# MCB-MTS-Dragonfly-v2_0_0.net
KiCad netlist of a schematic drawn in EAGLE
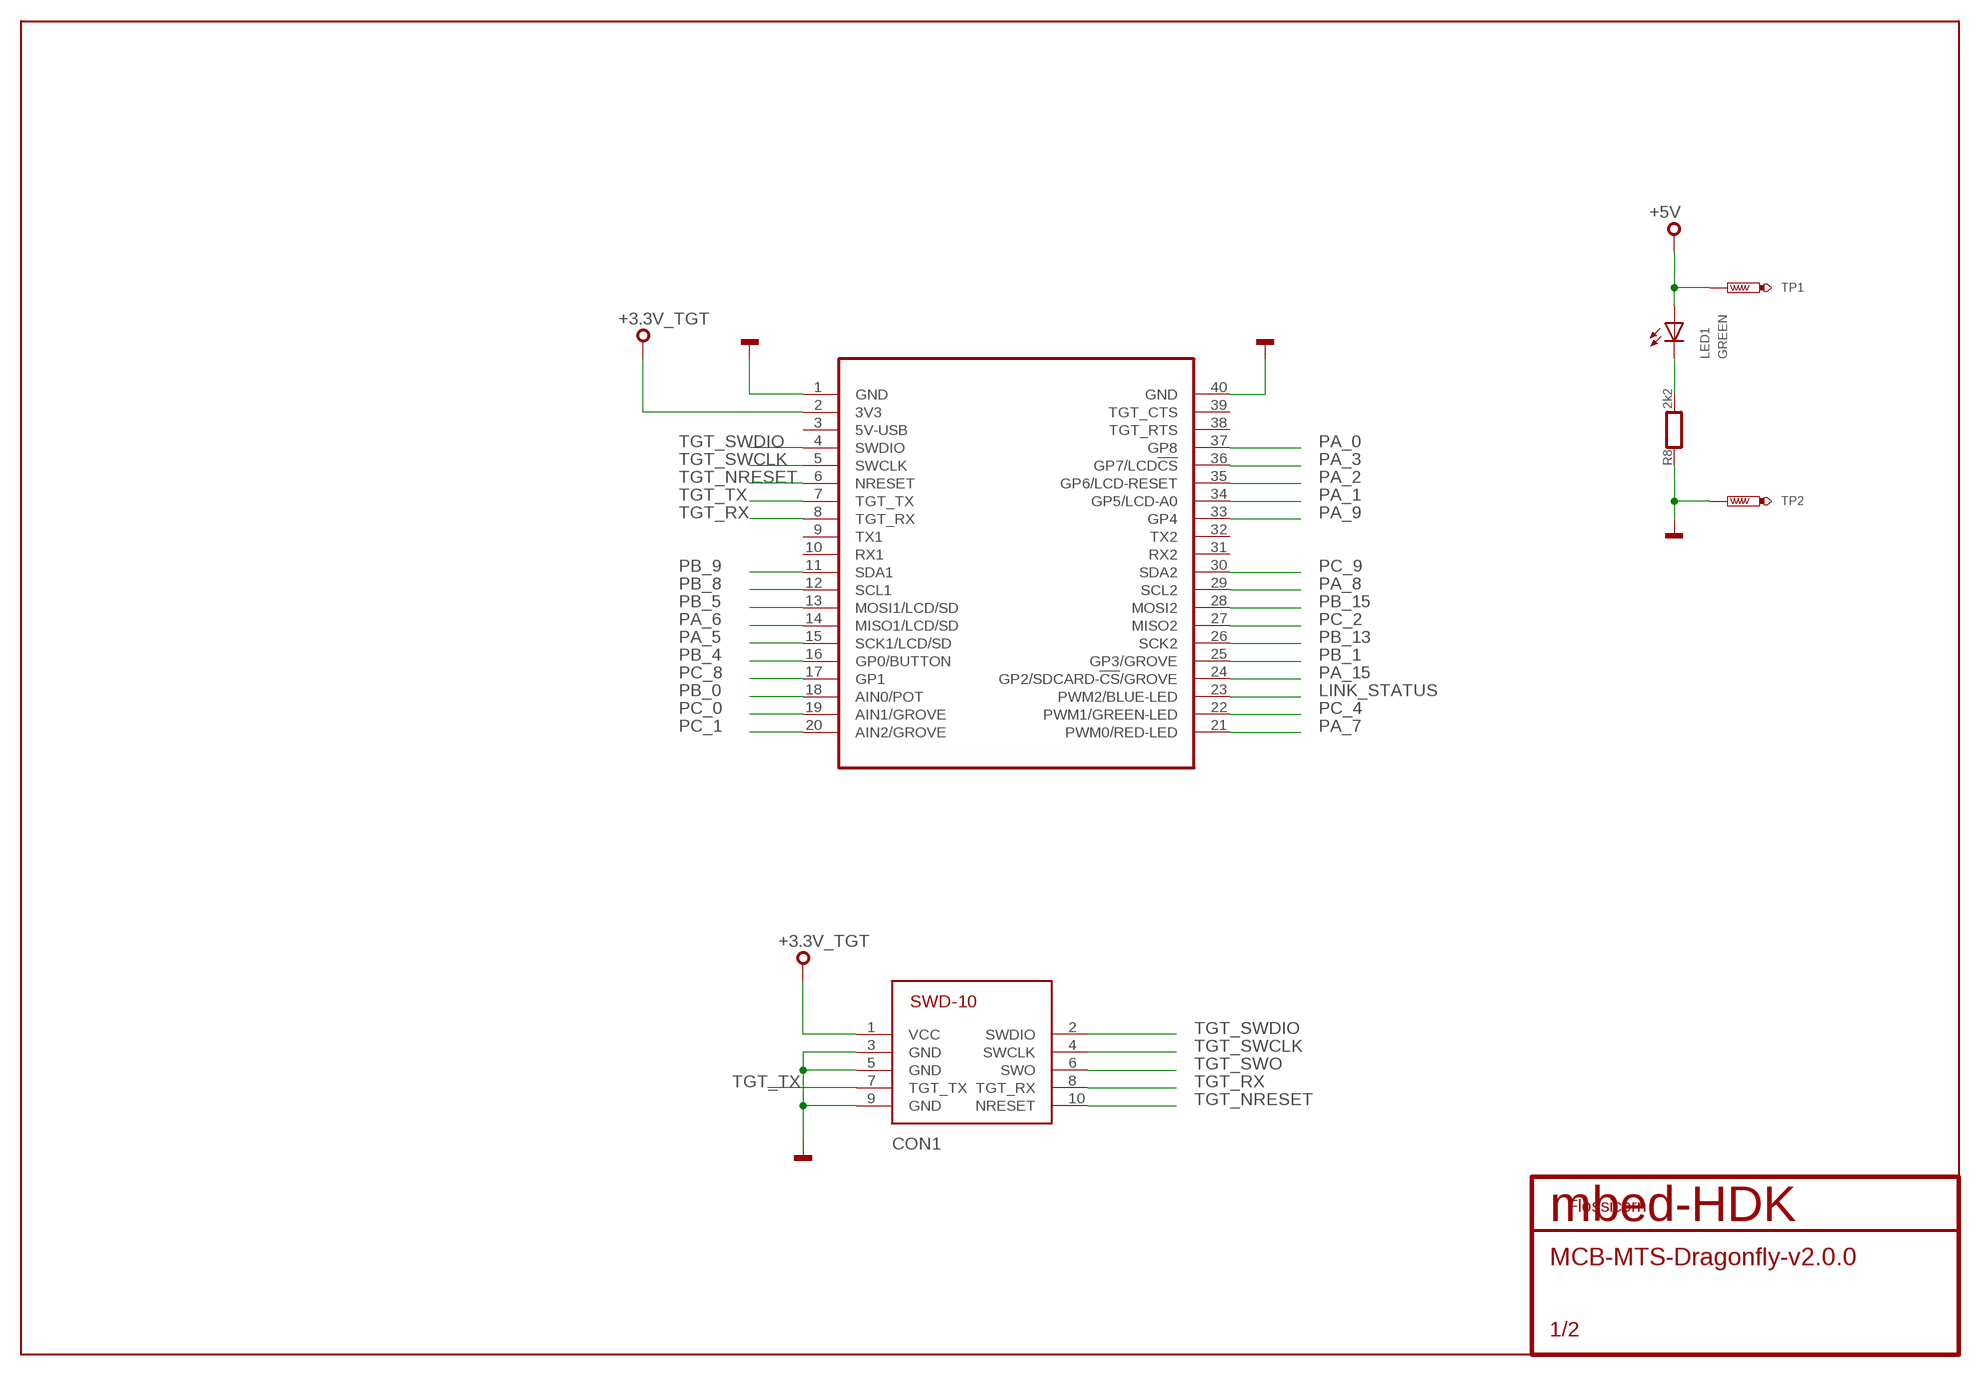
[diagram p0: schematic, sheet 1]
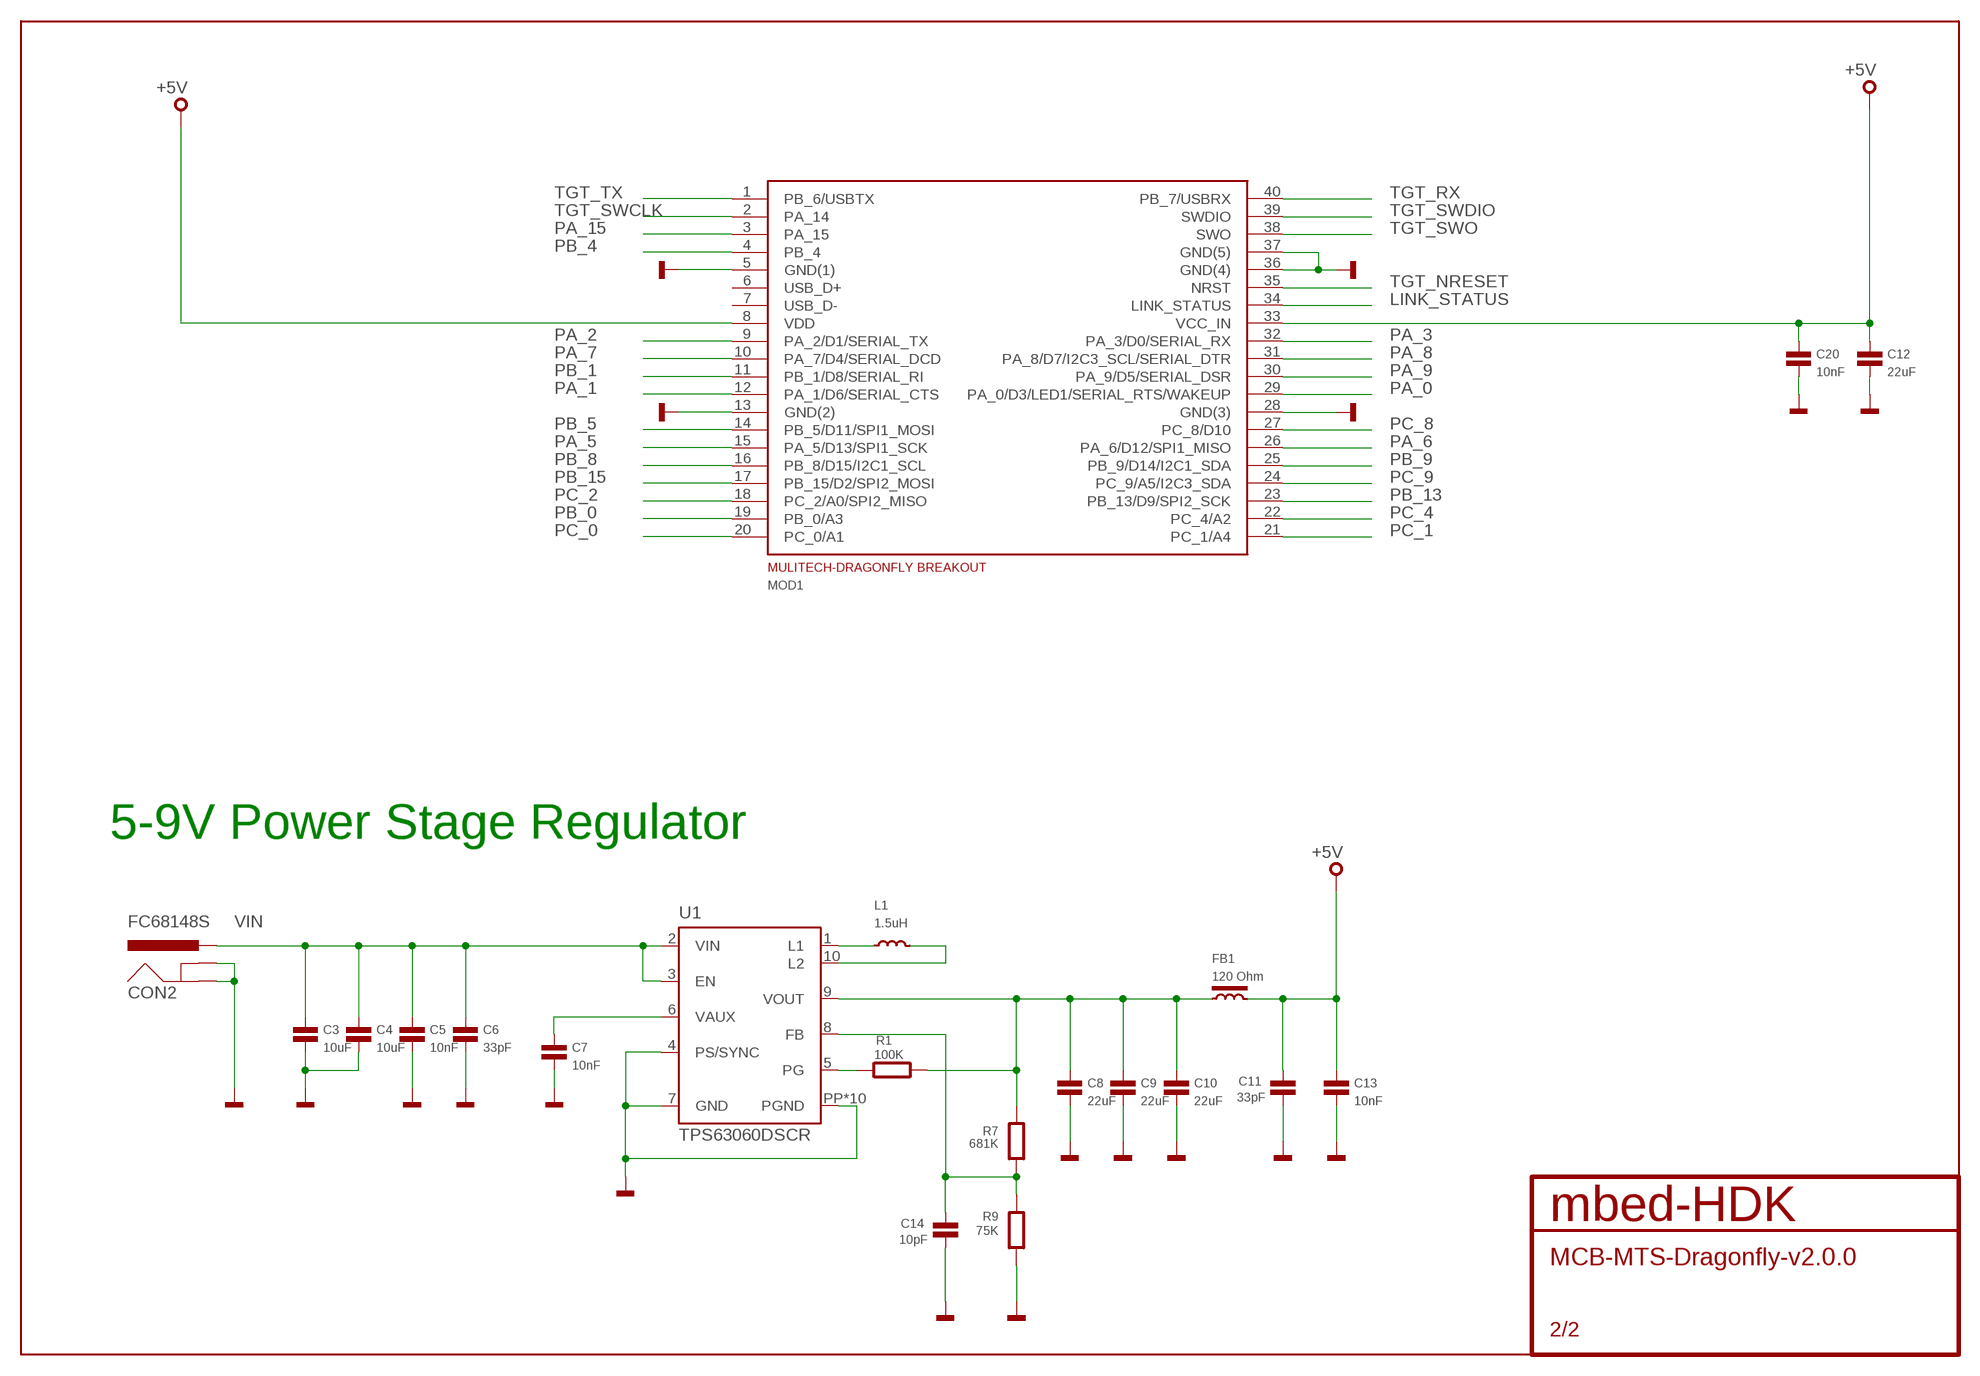
[diagram p1: schematic, sheet 2]

(export (version "E")
  (design (tool "Eeschema 10.0.6"))
  (components
    (comp (ref "CON1")
      (value "SWD-10/TC2050_SMD")
      (footprint "eagle-import:FTSH-105-02")
      (libsource (lib "eagle-import") (part "SWD-10/TC2050_SMD"))
    )
    (comp (ref "LED1")
      (value "GREEN")
      (footprint "eagle-import:CHIPLED_0603")
      (fields (field (name "MF") "Wurth Electronics Inc"))
      (libsource (lib "eagle-import") (part "SMD_LED0603"))
    )
    (comp (ref "MOD2")
      (value "MODULE_DAUGHTER")
      (footprint "eagle-import:MODULE_DAUGHTER")
      (libsource (lib "eagle-import") (part "MODULE_DAUGHTER"))
    )
    (comp (ref "R8")
      (value "2k2")
      (footprint "eagle-import:0603")
      (libsource (lib "eagle-import") (part "RESISTOR0603"))
    )
    (comp (ref "SS1")
      (value "FLOSSICORN0.5")
      (footprint "eagle-import:FLOSSICORN-0.5")
      (libsource (lib "eagle-import") (part "FLOSSICORN0.5"))
    )
    (comp (ref "TP1")
      (value "TEST-POINT-50R-PTH")
      (footprint "eagle-import:TP50-PTH")
      (libsource (lib "eagle-import") (part "TEST-POINT-50R-PTH"))
    )
    (comp (ref "TP2")
      (value "TEST-POINT-50R-PTH")
      (footprint "eagle-import:TP50-PTH")
      (libsource (lib "eagle-import") (part "TEST-POINT-50R-PTH"))
    )
    (comp (ref "C3")
      (value "10uF")
      (footprint "eagle-import:0603")
      (libsource (lib "eagle-import") (part "CAPACITOR0603"))
    )
    (comp (ref "C4")
      (value "10uF")
      (footprint "eagle-import:0603")
      (libsource (lib "eagle-import") (part "CAPACITOR0603"))
    )
    (comp (ref "C5")
      (value "10nF")
      (footprint "eagle-import:0603")
      (libsource (lib "eagle-import") (part "CAPACITOR0603"))
    )
    (comp (ref "C6")
      (value "33pF")
      (footprint "eagle-import:0603")
      (libsource (lib "eagle-import") (part "CAPACITOR0603"))
    )
    (comp (ref "C7")
      (value "10nF")
      (footprint "eagle-import:0603")
      (libsource (lib "eagle-import") (part "CAPACITOR0603"))
    )
    (comp (ref "C8")
      (value "22uF")
      (footprint "eagle-import:0603")
      (libsource (lib "eagle-import") (part "CAPACITOR0603"))
    )
    (comp (ref "C9")
      (value "22uF")
      (footprint "eagle-import:0603")
      (libsource (lib "eagle-import") (part "CAPACITOR0603"))
    )
    (comp (ref "C10")
      (value "22uF")
      (footprint "eagle-import:0603")
      (libsource (lib "eagle-import") (part "CAPACITOR0603"))
    )
    (comp (ref "C11")
      (value "33pF")
      (footprint "eagle-import:0603")
      (libsource (lib "eagle-import") (part "CAPACITOR0603"))
    )
    (comp (ref "C12")
      (value "22uF")
      (footprint "eagle-import:0603")
      (libsource (lib "eagle-import") (part "CAPACITOR0603"))
    )
    (comp (ref "C13")
      (value "10nF")
      (footprint "eagle-import:0603")
      (libsource (lib "eagle-import") (part "CAPACITOR0603"))
    )
    (comp (ref "C14")
      (value "10pF")
      (footprint "eagle-import:0603")
      (libsource (lib "eagle-import") (part "CAPACITOR0603"))
    )
    (comp (ref "C20")
      (value "10nF")
      (footprint "eagle-import:0603")
      (libsource (lib "eagle-import") (part "CAPACITOR0603"))
    )
    (comp (ref "CON2")
      (value "FC68148S")
      (footprint "eagle-import:FC68148S")
      (libsource (lib "eagle-import") (part "FC68148S"))
    )
    (comp (ref "FB1")
      (value "120 Ohm")
      (footprint "eagle-import:0603")
      (libsource (lib "eagle-import") (part "FERRITE0603"))
    )
    (comp (ref "L1")
      (value "1.5uH")
      (footprint "eagle-import:XFL4020-472MEC")
      (fields (field (name "MF") "CoilCraft"))
      (libsource (lib "eagle-import") (part "INDUCTORXFL4020"))
    )
    (comp (ref "MOD1")
      (value "MULITECH-DRAGONFLY-BREAKOUT")
      (footprint "eagle-import:MULITECH-DRAGONFLY-BREAKOUT")
      (fields (field (name "MF") "Hirose"))
      (libsource (lib "eagle-import") (part "MULITECH-DRAGONFLY-BREAKOUT"))
    )
    (comp (ref "R1")
      (value "100K")
      (footprint "eagle-import:0402")
      (libsource (lib "eagle-import") (part "mbed-HDK-RLCQ_RESISTOR0402"))
    )
    (comp (ref "R7")
      (value "681K")
      (footprint "eagle-import:0402")
      (libsource (lib "eagle-import") (part "mbed-HDK-RLCQ_RESISTOR0402"))
    )
    (comp (ref "R9")
      (value "75K")
      (footprint "eagle-import:0402")
      (libsource (lib "eagle-import") (part "mbed-HDK-RLCQ_RESISTOR0402"))
    )
    (comp (ref "U1")
      (value "TPS63060DSCR")
      (footprint "eagle-import:DSC-S-PWSON-N10")
      (fields (field (name "MF") "TEXAS INSTRUMENTS"))
      (libsource (lib "eagle-import") (part "TPS63060DSCR"))
    )
  )
  (nets
    (net (code "1") (name "+3.3V_TGT") (class "Default")
      (node (ref "CON1") (pin "1") (pinfunction "VCC_1") (pintype "bidirectional"))
      (node (ref "MOD2") (pin "2") (pinfunction "3V3_2") (pintype "bidirectional"))
    )
    (net (code "2") (name "+5V") (class "Default")
      (node (ref "C11") (pin "1") (pinfunction "P$1_1") (pintype "passive"))
      (node (ref "C12") (pin "1") (pinfunction "P$1_1") (pintype "passive"))
      (node (ref "C13") (pin "1") (pinfunction "P$1_1") (pintype "passive"))
      (node (ref "C20") (pin "1") (pinfunction "P$1_1") (pintype "passive"))
      (node (ref "FB1") (pin "2") (pinfunction "P$2_2") (pintype "bidirectional"))
      (node (ref "LED1") (pin "A") (pinfunction "A_A") (pintype "passive"))
      (node (ref "MOD1") (pin "33") (pinfunction "VCC_IN_33") (pintype "bidirectional"))
      (node (ref "MOD1") (pin "8") (pinfunction "VDD_8") (pintype "bidirectional"))
      (node (ref "TP1") (pin "TP") (pinfunction "TP_TP") (pintype "input"))
    )
    (net (code "3") (name "GND") (class "Default")
      (node (ref "C10") (pin "2") (pinfunction "P$2_2") (pintype "passive"))
      (node (ref "C11") (pin "2") (pinfunction "P$2_2") (pintype "passive"))
      (node (ref "C12") (pin "2") (pinfunction "P$2_2") (pintype "passive"))
      (node (ref "C13") (pin "2") (pinfunction "P$2_2") (pintype "passive"))
      (node (ref "C14") (pin "2") (pinfunction "P$2_2") (pintype "passive"))
      (node (ref "C20") (pin "2") (pinfunction "P$2_2") (pintype "passive"))
      (node (ref "C3") (pin "2") (pinfunction "P$2_2") (pintype "passive"))
      (node (ref "C4") (pin "2") (pinfunction "P$2_2") (pintype "passive"))
      (node (ref "C5") (pin "2") (pinfunction "P$2_2") (pintype "passive"))
      (node (ref "C6") (pin "2") (pinfunction "P$2_2") (pintype "passive"))
      (node (ref "C7") (pin "2") (pinfunction "P$2_2") (pintype "passive"))
      (node (ref "C8") (pin "2") (pinfunction "P$2_2") (pintype "passive"))
      (node (ref "C9") (pin "2") (pinfunction "P$2_2") (pintype "passive"))
      (node (ref "CON1") (pin "3") (pinfunction "GND_3") (pintype "bidirectional"))
      (node (ref "CON1") (pin "5") (pinfunction "GND_5") (pintype "bidirectional"))
      (node (ref "CON1") (pin "9") (pinfunction "GND_9") (pintype "bidirectional"))
      (node (ref "CON2") (pin "2") (pinfunction "GNDBREAK_2") (pintype "bidirectional"))
      (node (ref "CON2") (pin "3") (pinfunction "GND_3") (pintype "bidirectional"))
      (node (ref "MOD1") (pin "13") (pinfunction "GND(2)_13") (pintype "bidirectional"))
      (node (ref "MOD1") (pin "28") (pinfunction "GND(3)_28") (pintype "bidirectional"))
      (node (ref "MOD1") (pin "36") (pinfunction "GND(4)_36") (pintype "bidirectional"))
      (node (ref "MOD1") (pin "37") (pinfunction "GND(5)_37") (pintype "bidirectional"))
      (node (ref "MOD1") (pin "5") (pinfunction "GND(1)_5") (pintype "bidirectional"))
      (node (ref "MOD2") (pin "1") (pinfunction "GND_1") (pintype "bidirectional"))
      (node (ref "MOD2") (pin "40") (pinfunction "GND_40") (pintype "bidirectional"))
      (node (ref "R8") (pin "1") (pinfunction "P$1_1") (pintype "passive"))
      (node (ref "R9") (pin "1") (pinfunction "P$1_1") (pintype "passive"))
      (node (ref "TP2") (pin "TP") (pinfunction "TP_TP") (pintype "input"))
      (node (ref "U1") (pin "4") (pinfunction "PS/SYNC_4") (pintype "input"))
      (node (ref "U1") (pin "7") (pinfunction "GND_7") (pintype "input"))
      (node (ref "U1") (pin "PP") (pinfunction "PGND_PP") (pintype "power_in"))
      (node (ref "U1") (pin "PP@1") (pinfunction "PGND_PP@1") (pintype "power_in"))
      (node (ref "U1") (pin "PP@10") (pinfunction "PGND_PP@10") (pintype "power_in"))
      (node (ref "U1") (pin "PP@2") (pinfunction "PGND_PP@2") (pintype "power_in"))
      (node (ref "U1") (pin "PP@3") (pinfunction "PGND_PP@3") (pintype "power_in"))
      (node (ref "U1") (pin "PP@4") (pinfunction "PGND_PP@4") (pintype "power_in"))
      (node (ref "U1") (pin "PP@5") (pinfunction "PGND_PP@5") (pintype "power_in"))
      (node (ref "U1") (pin "PP@7") (pinfunction "PGND_PP@7") (pintype "power_in"))
      (node (ref "U1") (pin "PP@8") (pinfunction "PGND_PP@8") (pintype "power_in"))
      (node (ref "U1") (pin "PP@9") (pinfunction "PGND_PP@9") (pintype "power_in"))
    )
    (net (code "4") (name "LINK_STATUS") (class "Default")
      (node (ref "MOD1") (pin "34") (pinfunction "LINK_STATUS_34") (pintype "bidirectional"))
      (node (ref "MOD2") (pin "23") (pinfunction "PWM2/BLUE-LED_23") (pintype "bidirectional"))
    )
    (net (code "5") (name "Net-(C7-P$1)") (class "Default")
      (node (ref "C7") (pin "1") (pinfunction "P$1_1") (pintype "passive"))
      (node (ref "U1") (pin "6") (pinfunction "VAUX_6") (pintype "power_in"))
    )
    (net (code "6") (name "Net-(C10-P$1)") (class "Default")
      (node (ref "C10") (pin "1") (pinfunction "P$1_1") (pintype "passive"))
      (node (ref "C8") (pin "1") (pinfunction "P$1_1") (pintype "passive"))
      (node (ref "C9") (pin "1") (pinfunction "P$1_1") (pintype "passive"))
      (node (ref "FB1") (pin "1") (pinfunction "P$1_1") (pintype "bidirectional"))
      (node (ref "R1") (pin "2") (pinfunction "P$2_2") (pintype "passive"))
      (node (ref "R7") (pin "2") (pinfunction "P$2_2") (pintype "passive"))
      (node (ref "U1") (pin "9") (pinfunction "VOUT_9") (pintype "output"))
    )
    (net (code "7") (name "Net-(C14-P$1)") (class "Default")
      (node (ref "C14") (pin "1") (pinfunction "P$1_1") (pintype "passive"))
      (node (ref "R7") (pin "1") (pinfunction "P$1_1") (pintype "passive"))
      (node (ref "R9") (pin "2") (pinfunction "P$2_2") (pintype "passive"))
      (node (ref "U1") (pin "8") (pinfunction "FB_8") (pintype "input"))
    )
    (net (code "8") (name "Net-(R1-P$1)") (class "Default")
      (node (ref "R1") (pin "1") (pinfunction "P$1_1") (pintype "passive"))
      (node (ref "U1") (pin "5") (pinfunction "PG_5") (pintype "output"))
    )
    (net (code "9") (name "Net-(R8-P$2)") (class "Default")
      (node (ref "LED1") (pin "C") (pinfunction "C_C") (pintype "passive"))
      (node (ref "R8") (pin "2") (pinfunction "P$2_2") (pintype "passive"))
    )
    (net (code "10") (name "Net-(U1-L1)") (class "Default")
      (node (ref "L1") (pin "P$1") (pinfunction "P$1_P$1") (pintype "bidirectional"))
      (node (ref "U1") (pin "1") (pinfunction "L1_1") (pintype "input"))
    )
    (net (code "11") (name "Net-(U1-L2)") (class "Default")
      (node (ref "L1") (pin "P$2") (pinfunction "P$2_P$2") (pintype "bidirectional"))
      (node (ref "U1") (pin "10") (pinfunction "L2_10") (pintype "input"))
    )
    (net (code "12") (name "PA_0") (class "Default")
      (node (ref "MOD1") (pin "29") (pinfunction "PA_0/D3/LED1/SERIAL_RTS/WAKEUP_29") (pintype "bidirectional"))
      (node (ref "MOD2") (pin "37") (pinfunction "GP8_37") (pintype "bidirectional"))
    )
    (net (code "13") (name "PA_1") (class "Default")
      (node (ref "MOD1") (pin "12") (pinfunction "PA_1/D6/SERIAL_CTS_12") (pintype "bidirectional"))
      (node (ref "MOD2") (pin "34") (pinfunction "GP5/LCD-A0_34") (pintype "bidirectional"))
    )
    (net (code "14") (name "PA_2") (class "Default")
      (node (ref "MOD1") (pin "9") (pinfunction "PA_2/D1/SERIAL_TX_9") (pintype "bidirectional"))
      (node (ref "MOD2") (pin "35") (pinfunction "GP6/LCD-RESET_35") (pintype "bidirectional"))
    )
    (net (code "15") (name "PA_3") (class "Default")
      (node (ref "MOD1") (pin "32") (pinfunction "PA_3/D0/SERIAL_RX_32") (pintype "bidirectional"))
      (node (ref "MOD2") (pin "36") (pinfunction "GP7/LCD~{CS}_36") (pintype "bidirectional"))
    )
    (net (code "16") (name "PA_5") (class "Default")
      (node (ref "MOD1") (pin "15") (pinfunction "PA_5/D13/SPI1_SCK_15") (pintype "bidirectional"))
      (node (ref "MOD2") (pin "15") (pinfunction "SCK1/LCD/SD_15") (pintype "bidirectional"))
    )
    (net (code "17") (name "PA_6") (class "Default")
      (node (ref "MOD1") (pin "26") (pinfunction "PA_6/D12/SPI1_MISO_26") (pintype "bidirectional"))
      (node (ref "MOD2") (pin "14") (pinfunction "MISO1/LCD/SD_14") (pintype "bidirectional"))
    )
    (net (code "18") (name "PA_7") (class "Default")
      (node (ref "MOD1") (pin "10") (pinfunction "PA_7/D4/SERIAL_DCD_10") (pintype "bidirectional"))
      (node (ref "MOD2") (pin "21") (pinfunction "PWM0/RED-LED_21") (pintype "bidirectional"))
    )
    (net (code "19") (name "PA_8") (class "Default")
      (node (ref "MOD1") (pin "31") (pinfunction "PA_8/D7/I2C3_SCL/SERIAL_DTR_31") (pintype "bidirectional"))
      (node (ref "MOD2") (pin "29") (pinfunction "SCL2_29") (pintype "bidirectional"))
    )
    (net (code "20") (name "PA_9") (class "Default")
      (node (ref "MOD1") (pin "30") (pinfunction "PA_9/D5/SERIAL_DSR_30") (pintype "bidirectional"))
      (node (ref "MOD2") (pin "33") (pinfunction "GP4_33") (pintype "bidirectional"))
    )
    (net (code "21") (name "PA_15") (class "Default")
      (node (ref "MOD1") (pin "3") (pinfunction "PA_15_3") (pintype "bidirectional"))
      (node (ref "MOD2") (pin "24") (pinfunction "GP2/SDCARD-~{CS}/GROVE_24") (pintype "bidirectional"))
    )
    (net (code "22") (name "PB_0") (class "Default")
      (node (ref "MOD1") (pin "19") (pinfunction "PB_0/A3_19") (pintype "bidirectional"))
      (node (ref "MOD2") (pin "18") (pinfunction "AIN0/POT_18") (pintype "bidirectional"))
    )
    (net (code "23") (name "PB_1") (class "Default")
      (node (ref "MOD1") (pin "11") (pinfunction "PB_1/D8/SERIAL_RI_11") (pintype "bidirectional"))
      (node (ref "MOD2") (pin "25") (pinfunction "GP3/GROVE_25") (pintype "bidirectional"))
    )
    (net (code "24") (name "PB_4") (class "Default")
      (node (ref "MOD1") (pin "4") (pinfunction "PB_4_4") (pintype "bidirectional"))
      (node (ref "MOD2") (pin "16") (pinfunction "GP0/BUTTON_16") (pintype "bidirectional"))
    )
    (net (code "25") (name "PB_5") (class "Default")
      (node (ref "MOD1") (pin "14") (pinfunction "PB_5/D11/SPI1_MOSI_14") (pintype "bidirectional"))
      (node (ref "MOD2") (pin "13") (pinfunction "MOSI1/LCD/SD_13") (pintype "bidirectional"))
    )
    (net (code "26") (name "PB_8") (class "Default")
      (node (ref "MOD1") (pin "16") (pinfunction "PB_8/D15/I2C1_SCL_16") (pintype "bidirectional"))
      (node (ref "MOD2") (pin "12") (pinfunction "SCL1_12") (pintype "bidirectional"))
    )
    (net (code "27") (name "PB_9") (class "Default")
      (node (ref "MOD1") (pin "25") (pinfunction "PB_9/D14/I2C1_SDA_25") (pintype "bidirectional"))
      (node (ref "MOD2") (pin "11") (pinfunction "SDA1_11") (pintype "bidirectional"))
    )
    (net (code "28") (name "PB_13") (class "Default")
      (node (ref "MOD1") (pin "23") (pinfunction "PB_13/D9/SPI2_SCK_23") (pintype "bidirectional"))
      (node (ref "MOD2") (pin "26") (pinfunction "SCK2_26") (pintype "bidirectional"))
    )
    (net (code "29") (name "PB_15") (class "Default")
      (node (ref "MOD1") (pin "17") (pinfunction "PB_15/D2/SPI2_MOSI_17") (pintype "bidirectional"))
      (node (ref "MOD2") (pin "28") (pinfunction "MOSI2_28") (pintype "bidirectional"))
    )
    (net (code "30") (name "PC_0") (class "Default")
      (node (ref "MOD1") (pin "20") (pinfunction "PC_0/A1_20") (pintype "bidirectional"))
      (node (ref "MOD2") (pin "19") (pinfunction "AIN1/GROVE_19") (pintype "bidirectional"))
    )
    (net (code "31") (name "PC_1") (class "Default")
      (node (ref "MOD1") (pin "21") (pinfunction "PC_1/A4_21") (pintype "bidirectional"))
      (node (ref "MOD2") (pin "20") (pinfunction "AIN2/GROVE_20") (pintype "bidirectional"))
    )
    (net (code "32") (name "PC_2") (class "Default")
      (node (ref "MOD1") (pin "18") (pinfunction "PC_2/A0/SPI2_MISO_18") (pintype "bidirectional"))
      (node (ref "MOD2") (pin "27") (pinfunction "MISO2_27") (pintype "bidirectional"))
    )
    (net (code "33") (name "PC_4") (class "Default")
      (node (ref "MOD1") (pin "22") (pinfunction "PC_4/A2_22") (pintype "bidirectional"))
      (node (ref "MOD2") (pin "22") (pinfunction "PWM1/GREEN-LED_22") (pintype "bidirectional"))
    )
    (net (code "34") (name "PC_8") (class "Default")
      (node (ref "MOD1") (pin "27") (pinfunction "PC_8/D10_27") (pintype "bidirectional"))
      (node (ref "MOD2") (pin "17") (pinfunction "GP1_17") (pintype "bidirectional"))
    )
    (net (code "35") (name "PC_9") (class "Default")
      (node (ref "MOD1") (pin "24") (pinfunction "PC_9/A5/I2C3_SDA_24") (pintype "bidirectional"))
      (node (ref "MOD2") (pin "30") (pinfunction "SDA2_30") (pintype "bidirectional"))
    )
    (net (code "36") (name "TGT_NRESET") (class "Default")
      (node (ref "CON1") (pin "10") (pinfunction "NRESET_10") (pintype "bidirectional"))
      (node (ref "MOD1") (pin "35") (pinfunction "NRST_35") (pintype "bidirectional"))
      (node (ref "MOD2") (pin "6") (pinfunction "NRESET_6") (pintype "bidirectional"))
    )
    (net (code "37") (name "TGT_RX") (class "Default")
      (node (ref "CON1") (pin "8") (pinfunction "TGT_RX_8") (pintype "bidirectional"))
      (node (ref "MOD1") (pin "40") (pinfunction "PB_7/USBRX_40") (pintype "bidirectional"))
      (node (ref "MOD2") (pin "8") (pinfunction "TGT_RX_8") (pintype "bidirectional"))
    )
    (net (code "38") (name "TGT_SWCLK") (class "Default")
      (node (ref "CON1") (pin "4") (pinfunction "SWCLK_4") (pintype "bidirectional"))
      (node (ref "MOD1") (pin "2") (pinfunction "PA_14_2") (pintype "bidirectional"))
      (node (ref "MOD2") (pin "5") (pinfunction "SWCLK_5") (pintype "bidirectional"))
    )
    (net (code "39") (name "TGT_SWDIO") (class "Default")
      (node (ref "CON1") (pin "2") (pinfunction "SWDIO_2") (pintype "bidirectional"))
      (node (ref "MOD1") (pin "39") (pinfunction "SWDIO_39") (pintype "bidirectional"))
      (node (ref "MOD2") (pin "4") (pinfunction "SWDIO_4") (pintype "bidirectional"))
    )
    (net (code "40") (name "TGT_SWO") (class "Default")
      (node (ref "CON1") (pin "6") (pinfunction "SWO_6") (pintype "bidirectional"))
      (node (ref "MOD1") (pin "38") (pinfunction "SWO_38") (pintype "bidirectional"))
    )
    (net (code "41") (name "TGT_TX") (class "Default")
      (node (ref "CON1") (pin "7") (pinfunction "TGT_TX_7") (pintype "bidirectional"))
      (node (ref "MOD1") (pin "1") (pinfunction "PB_6/USBTX_1") (pintype "bidirectional"))
      (node (ref "MOD2") (pin "7") (pinfunction "TGT_TX_7") (pintype "bidirectional"))
    )
    (net (code "42") (name "VIN") (class "Default")
      (node (ref "C3") (pin "1") (pinfunction "P$1_1") (pintype "passive"))
      (node (ref "C4") (pin "1") (pinfunction "P$1_1") (pintype "passive"))
      (node (ref "C5") (pin "1") (pinfunction "P$1_1") (pintype "passive"))
      (node (ref "C6") (pin "1") (pinfunction "P$1_1") (pintype "passive"))
      (node (ref "CON2") (pin "1-1") (pinfunction "PWR_1-1") (pintype "bidirectional"))
      (node (ref "CON2") (pin "1-2") (pinfunction "PWR_1-2") (pintype "bidirectional"))
      (node (ref "U1") (pin "2") (pinfunction "VIN_2") (pintype "input"))
      (node (ref "U1") (pin "3") (pinfunction "EN_3") (pintype "input"))
    )
    (net (code "43") (name "unconnected-(MOD1-USB_D+-Pad6)") (class "Default")
      (node (ref "MOD1") (pin "6") (pinfunction "USB_D+_6") (pintype "bidirectional"))
    )
    (net (code "44") (name "unconnected-(MOD1-USB_D--Pad7)") (class "Default")
      (node (ref "MOD1") (pin "7") (pinfunction "USB_D-_7") (pintype "bidirectional"))
    )
    (net (code "45") (name "unconnected-(MOD2-5V-USB-Pad3)") (class "Default")
      (node (ref "MOD2") (pin "3") (pinfunction "5V-USB_3") (pintype "bidirectional"))
    )
    (net (code "46") (name "unconnected-(MOD2-RX1-Pad10)") (class "Default")
      (node (ref "MOD2") (pin "10") (pinfunction "RX1_10") (pintype "bidirectional"))
    )
    (net (code "47") (name "unconnected-(MOD2-RX2-Pad31)") (class "Default")
      (node (ref "MOD2") (pin "31") (pinfunction "RX2_31") (pintype "bidirectional"))
    )
    (net (code "48") (name "unconnected-(MOD2-TGT_CTS-Pad39)") (class "Default")
      (node (ref "MOD2") (pin "39") (pinfunction "TGT_CTS_39") (pintype "bidirectional"))
    )
    (net (code "49") (name "unconnected-(MOD2-TGT_RTS-Pad38)") (class "Default")
      (node (ref "MOD2") (pin "38") (pinfunction "TGT_RTS_38") (pintype "bidirectional"))
    )
    (net (code "50") (name "unconnected-(MOD2-TX1-Pad9)") (class "Default")
      (node (ref "MOD2") (pin "9") (pinfunction "TX1_9") (pintype "bidirectional"))
    )
    (net (code "51") (name "unconnected-(MOD2-TX2-Pad32)") (class "Default")
      (node (ref "MOD2") (pin "32") (pinfunction "TX2_32") (pintype "bidirectional"))
    )
  )
)
